# ADCs.net
KiCad netlist of a schematic drawn in Altium Designer
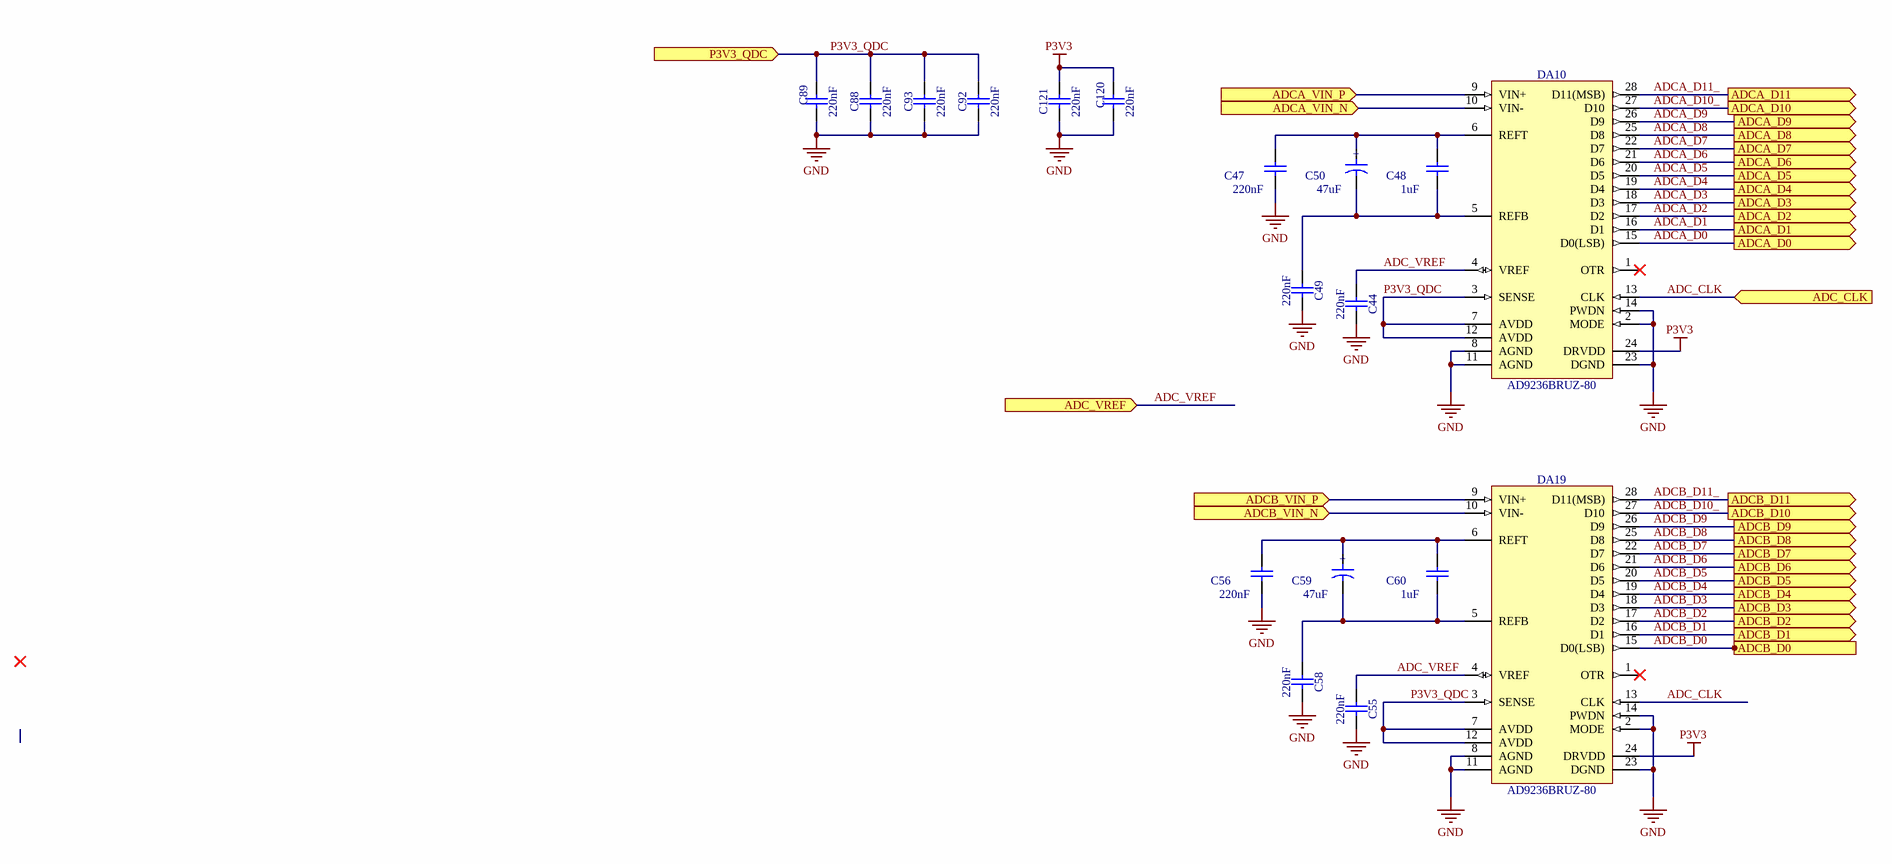
[diagram p0: ADCs.SchDoc]

(export (version "E")
  (design (tool "Eeschema 10.0.6"))
  (components
    (comp (ref "C44")
      (value "220nF")
      (footprint "CAPC2012X135N")
      (description "Non-polarised capacitor")
      (fields
        (field (name "PART NUMBER") "CC0805_220NF_50V_10%_X7R")
        (field (name "VOLTAGE") "50V")
        (field (name "AUTHOR") "CERN DEM JLC")
      )
      (libsource (lib "Capacitors") (part "Capacitor - non polarized"))
    )
    (comp (ref "C47")
      (value "220nF")
      (footprint "CAPC2012X135N")
      (description "Non-polarised capacitor")
      (fields
        (field (name "PART NUMBER") "CC0805_220NF_50V_10%_X7R")
        (field (name "VOLTAGE") "50V")
        (field (name "AUTHOR") "CERN DEM JLC")
      )
      (libsource (lib "Capacitors") (part "Capacitor - non polarized"))
    )
    (comp (ref "C48")
      (value "1uF")
      (footprint "CAPC2012X140N")
      (description "Non-polarised capacitor")
      (fields
        (field (name "PART NUMBER") "CC0805_1UF_25V_10%_X7R")
        (field (name "VOLTAGE") "25V")
        (field (name "AUTHOR") "CERN DEM JLC")
      )
      (libsource (lib "Capacitors") (part "Capacitor - non polarized"))
    )
    (comp (ref "C49")
      (value "220nF")
      (footprint "CAPC2012X135N")
      (description "Non-polarised capacitor")
      (fields
        (field (name "PART NUMBER") "CC0805_220NF_50V_10%_X7R")
        (field (name "VOLTAGE") "50V")
        (field (name "AUTHOR") "CERN DEM JLC")
      )
      (libsource (lib "Capacitors") (part "Capacitor - non polarized"))
    )
    (comp (ref "C50")
      (value "47uF")
      (footprint "CAPMP3528X120N")
      (description "Polarised capacitor")
      (fields
        (field (name "PART NUMBER") "CTE3528-12_47UF_10V_20%_PANASONIC_TPG")
        (field (name "VOLTAGE") "10V")
        (field (name "AUTHOR") "CERN DEM JLC")
      )
      (libsource (lib "Capacitors") (part "Capacitor - polarized"))
    )
    (comp (ref "C55")
      (value "220nF")
      (footprint "CAPC2012X135N")
      (description "Non-polarised capacitor")
      (fields
        (field (name "PART NUMBER") "CC0805_220NF_50V_10%_X7R")
        (field (name "VOLTAGE") "50V")
        (field (name "AUTHOR") "CERN DEM JLC")
      )
      (libsource (lib "Capacitors") (part "Capacitor - non polarized"))
    )
    (comp (ref "C56")
      (value "220nF")
      (footprint "CAPC2012X135N")
      (description "Non-polarised capacitor")
      (fields
        (field (name "PART NUMBER") "CC0805_220NF_50V_10%_X7R")
        (field (name "VOLTAGE") "50V")
        (field (name "AUTHOR") "CERN DEM JLC")
      )
      (libsource (lib "Capacitors") (part "Capacitor - non polarized"))
    )
    (comp (ref "C58")
      (value "220nF")
      (footprint "CAPC2012X135N")
      (description "Non-polarised capacitor")
      (fields
        (field (name "PART NUMBER") "CC0805_220NF_50V_10%_X7R")
        (field (name "VOLTAGE") "50V")
        (field (name "AUTHOR") "CERN DEM JLC")
      )
      (libsource (lib "Capacitors") (part "Capacitor - non polarized"))
    )
    (comp (ref "C59")
      (value "47uF")
      (footprint "CAPMP3528X120N")
      (description "Polarised capacitor")
      (fields
        (field (name "PART NUMBER") "CTE3528-12_47UF_10V_20%_PANASONIC_TPG")
        (field (name "VOLTAGE") "10V")
        (field (name "AUTHOR") "CERN DEM JLC")
      )
      (libsource (lib "Capacitors") (part "Capacitor - polarized"))
    )
    (comp (ref "C60")
      (value "1uF")
      (footprint "CAPC2012X140N")
      (description "Non-polarised capacitor")
      (fields
        (field (name "PART NUMBER") "CC0805_1UF_25V_10%_X7R")
        (field (name "VOLTAGE") "25V")
        (field (name "AUTHOR") "CERN DEM JLC")
      )
      (libsource (lib "Capacitors") (part "Capacitor - non polarized"))
    )
    (comp (ref "C88")
      (value "220nF")
      (footprint "CAPC2012X135N")
      (description "Non-polarised capacitor")
      (fields
        (field (name "PART NUMBER") "CC0805_220NF_50V_10%_X7R")
        (field (name "VOLTAGE") "50V")
        (field (name "AUTHOR") "CERN DEM JLC")
      )
      (libsource (lib "Capacitors") (part "Capacitor - non polarized"))
    )
    (comp (ref "C89")
      (value "220nF")
      (footprint "CAPC2012X135N")
      (description "Non-polarised capacitor")
      (fields
        (field (name "PART NUMBER") "CC0805_220NF_50V_10%_X7R")
        (field (name "VOLTAGE") "50V")
        (field (name "AUTHOR") "CERN DEM JLC")
      )
      (libsource (lib "Capacitors") (part "Capacitor - non polarized"))
    )
    (comp (ref "C92")
      (value "220nF")
      (footprint "CAPC2012X135N")
      (description "Non-polarised capacitor")
      (fields
        (field (name "PART NUMBER") "CC0805_220NF_50V_10%_X7R")
        (field (name "VOLTAGE") "50V")
        (field (name "AUTHOR") "CERN DEM JLC")
      )
      (libsource (lib "Capacitors") (part "Capacitor - non polarized"))
    )
    (comp (ref "C93")
      (value "220nF")
      (footprint "CAPC2012X135N")
      (description "Non-polarised capacitor")
      (fields
        (field (name "PART NUMBER") "CC0805_220NF_50V_10%_X7R")
        (field (name "VOLTAGE") "50V")
        (field (name "AUTHOR") "CERN DEM JLC")
      )
      (libsource (lib "Capacitors") (part "Capacitor - non polarized"))
    )
    (comp (ref "C120")
      (value "220nF")
      (footprint "CAPC2012X135N")
      (description "Non-polarised capacitor")
      (fields
        (field (name "PART NUMBER") "CC0805_220NF_50V_10%_X7R")
        (field (name "VOLTAGE") "50V")
        (field (name "AUTHOR") "CERN DEM JLC")
      )
      (libsource (lib "Capacitors") (part "Capacitor - non polarized"))
    )
    (comp (ref "C121")
      (value "220nF")
      (footprint "CAPC2012X135N")
      (description "Non-polarised capacitor")
      (fields
        (field (name "PART NUMBER") "CC0805_220NF_50V_10%_X7R")
        (field (name "VOLTAGE") "50V")
        (field (name "AUTHOR") "CERN DEM JLC")
      )
      (libsource (lib "Capacitors") (part "Capacitor - non polarized"))
    )
    (comp (ref "DA10")
      (value "AD9236BRUZ-80")
      (footprint "SOP65P640X120-28N")
      (description "12-Bit, 80 MSPS 3 V ADC")
      (fields
        (field (name "MANUFACTURER") "ANALOG DEVICES")
        (field (name "MANUFACTURER PART NUMBER") "AD9235BRUZ-40")
        (field (name "AUTHOR") "CERN DEM HF")
      )
      (libsource (lib "ICs And Semiconductors") (part "AD9236BRU"))
    )
    (comp (ref "DA19")
      (value "AD9236BRUZ-80")
      (footprint "SOP65P640X120-28N")
      (description "12-Bit, 80 MSPS 3 V ADC")
      (fields
        (field (name "MANUFACTURER") "ANALOG DEVICES")
        (field (name "MANUFACTURER PART NUMBER") "AD9235BRUZ-40")
        (field (name "AUTHOR") "CERN DEM HF")
      )
      (libsource (lib "ICs And Semiconductors") (part "AD9236BRU"))
    )
  )
  (nets
    (net (code "1") (name "/ADCA_D0") (class "Default")
      (node (ref "DA10") (pin "15") (pinfunction "D0(LSB)_15") (pintype "output"))
    )
    (net (code "2") (name "/ADCA_D1") (class "Default")
      (node (ref "DA10") (pin "16") (pinfunction "D1_16") (pintype "output"))
    )
    (net (code "3") (name "/ADCA_D2") (class "Default")
      (node (ref "DA10") (pin "17") (pinfunction "D2_17") (pintype "output"))
    )
    (net (code "4") (name "/ADCA_D3") (class "Default")
      (node (ref "DA10") (pin "18") (pinfunction "D3_18") (pintype "output"))
    )
    (net (code "5") (name "/ADCA_D4") (class "Default")
      (node (ref "DA10") (pin "19") (pinfunction "D4_19") (pintype "output"))
    )
    (net (code "6") (name "/ADCA_D5") (class "Default")
      (node (ref "DA10") (pin "20") (pinfunction "D5_20") (pintype "output"))
    )
    (net (code "7") (name "/ADCA_D6") (class "Default")
      (node (ref "DA10") (pin "21") (pinfunction "D6_21") (pintype "output"))
    )
    (net (code "8") (name "/ADCA_D7") (class "Default")
      (node (ref "DA10") (pin "22") (pinfunction "D7_22") (pintype "output"))
    )
    (net (code "9") (name "/ADCA_D8") (class "Default")
      (node (ref "DA10") (pin "25") (pinfunction "D8_25") (pintype "output"))
    )
    (net (code "10") (name "/ADCA_D9") (class "Default")
      (node (ref "DA10") (pin "26") (pinfunction "D9_26") (pintype "output"))
    )
    (net (code "11") (name "/ADCA_D10_") (class "Default")
      (node (ref "DA10") (pin "27") (pinfunction "D10_27") (pintype "output"))
    )
    (net (code "12") (name "/ADCA_D11_") (class "Default")
      (node (ref "DA10") (pin "28") (pinfunction "D11(MSB)_28") (pintype "output"))
    )
    (net (code "13") (name "/ADCA_VIN_N") (class "Default")
      (node (ref "DA10") (pin "10") (pinfunction "VIN-_10") (pintype "input"))
    )
    (net (code "14") (name "/ADCA_VIN_P") (class "Default")
      (node (ref "DA10") (pin "9") (pinfunction "VIN+_9") (pintype "input"))
    )
    (net (code "15") (name "/ADCB_D0") (class "Default")
      (node (ref "DA19") (pin "15") (pinfunction "D0(LSB)_15") (pintype "output"))
    )
    (net (code "16") (name "/ADCB_D1") (class "Default")
      (node (ref "DA19") (pin "16") (pinfunction "D1_16") (pintype "output"))
    )
    (net (code "17") (name "/ADCB_D2") (class "Default")
      (node (ref "DA19") (pin "17") (pinfunction "D2_17") (pintype "output"))
    )
    (net (code "18") (name "/ADCB_D3") (class "Default")
      (node (ref "DA19") (pin "18") (pinfunction "D3_18") (pintype "output"))
    )
    (net (code "19") (name "/ADCB_D4") (class "Default")
      (node (ref "DA19") (pin "19") (pinfunction "D4_19") (pintype "output"))
    )
    (net (code "20") (name "/ADCB_D5") (class "Default")
      (node (ref "DA19") (pin "20") (pinfunction "D5_20") (pintype "output"))
    )
    (net (code "21") (name "/ADCB_D6") (class "Default")
      (node (ref "DA19") (pin "21") (pinfunction "D6_21") (pintype "output"))
    )
    (net (code "22") (name "/ADCB_D7") (class "Default")
      (node (ref "DA19") (pin "22") (pinfunction "D7_22") (pintype "output"))
    )
    (net (code "23") (name "/ADCB_D8") (class "Default")
      (node (ref "DA19") (pin "25") (pinfunction "D8_25") (pintype "output"))
    )
    (net (code "24") (name "/ADCB_D9") (class "Default")
      (node (ref "DA19") (pin "26") (pinfunction "D9_26") (pintype "output"))
    )
    (net (code "25") (name "/ADCB_D10_") (class "Default")
      (node (ref "DA19") (pin "27") (pinfunction "D10_27") (pintype "output"))
    )
    (net (code "26") (name "/ADCB_D11_") (class "Default")
      (node (ref "DA19") (pin "28") (pinfunction "D11(MSB)_28") (pintype "output"))
    )
    (net (code "27") (name "/ADCB_VIN_N") (class "Default")
      (node (ref "DA19") (pin "10") (pinfunction "VIN-_10") (pintype "input"))
    )
    (net (code "28") (name "/ADCB_VIN_P") (class "Default")
      (node (ref "DA19") (pin "9") (pinfunction "VIN+_9") (pintype "input"))
    )
    (net (code "29") (name "/ADC_CLK") (class "Default")
      (node (ref "DA10") (pin "13") (pinfunction "CLK_13") (pintype "input"))
      (node (ref "DA19") (pin "13") (pinfunction "CLK_13") (pintype "input"))
    )
    (net (code "30") (name "/ADC_VREF") (class "Default")
      (node (ref "C44") (pin "2") (pinfunction "2_2") (pintype "passive"))
      (node (ref "C55") (pin "2") (pinfunction "2_2") (pintype "passive"))
      (node (ref "DA10") (pin "4") (pinfunction "VREF_4") (pintype "bidirectional"))
      (node (ref "DA19") (pin "4") (pinfunction "VREF_4") (pintype "bidirectional"))
    )
    (net (code "31") (name "/P3V3_QDC") (class "Default")
      (node (ref "C88") (pin "2") (pinfunction "2_2") (pintype "passive"))
      (node (ref "C89") (pin "2") (pinfunction "2_2") (pintype "passive"))
      (node (ref "C92") (pin "2") (pinfunction "2_2") (pintype "passive"))
      (node (ref "C93") (pin "2") (pinfunction "2_2") (pintype "passive"))
      (node (ref "DA10") (pin "12") (pinfunction "AVDD_12") (pintype "power_in"))
      (node (ref "DA10") (pin "3") (pinfunction "SENSE_3") (pintype "input"))
      (node (ref "DA10") (pin "7") (pinfunction "AVDD_7") (pintype "power_in"))
      (node (ref "DA19") (pin "12") (pinfunction "AVDD_12") (pintype "power_in"))
      (node (ref "DA19") (pin "3") (pinfunction "SENSE_3") (pintype "input"))
      (node (ref "DA19") (pin "7") (pinfunction "AVDD_7") (pintype "power_in"))
    )
    (net (code "32") (name "GND") (class "Default")
      (node (ref "C120") (pin "1") (pinfunction "1_1") (pintype "passive"))
      (node (ref "C121") (pin "1") (pinfunction "1_1") (pintype "passive"))
      (node (ref "C44") (pin "1") (pinfunction "1_1") (pintype "passive"))
      (node (ref "C47") (pin "1") (pinfunction "1_1") (pintype "passive"))
      (node (ref "C49") (pin "1") (pinfunction "1_1") (pintype "passive"))
      (node (ref "C55") (pin "1") (pinfunction "1_1") (pintype "passive"))
      (node (ref "C56") (pin "1") (pinfunction "1_1") (pintype "passive"))
      (node (ref "C58") (pin "1") (pinfunction "1_1") (pintype "passive"))
      (node (ref "C88") (pin "1") (pinfunction "1_1") (pintype "passive"))
      (node (ref "C89") (pin "1") (pinfunction "1_1") (pintype "passive"))
      (node (ref "C92") (pin "1") (pinfunction "1_1") (pintype "passive"))
      (node (ref "C93") (pin "1") (pinfunction "1_1") (pintype "passive"))
      (node (ref "DA10") (pin "11") (pinfunction "AGND_11") (pintype "power_in"))
      (node (ref "DA10") (pin "14") (pinfunction "PWDN_14") (pintype "input"))
      (node (ref "DA10") (pin "2") (pinfunction "MODE_2") (pintype "input"))
      (node (ref "DA10") (pin "23") (pinfunction "DGND_23") (pintype "power_in"))
      (node (ref "DA10") (pin "8") (pinfunction "AGND_8") (pintype "power_in"))
      (node (ref "DA19") (pin "11") (pinfunction "AGND_11") (pintype "power_in"))
      (node (ref "DA19") (pin "14") (pinfunction "PWDN_14") (pintype "input"))
      (node (ref "DA19") (pin "2") (pinfunction "MODE_2") (pintype "input"))
      (node (ref "DA19") (pin "23") (pinfunction "DGND_23") (pintype "power_in"))
      (node (ref "DA19") (pin "8") (pinfunction "AGND_8") (pintype "power_in"))
    )
    (net (code "33") (name "Net-(DA10-REFB)") (class "Default")
      (node (ref "C48") (pin "1") (pinfunction "1_1") (pintype "passive"))
      (node (ref "C49") (pin "2") (pinfunction "2_2") (pintype "passive"))
      (node (ref "C50") (pin "2") (pinfunction "2_2") (pintype "passive"))
      (node (ref "DA10") (pin "5") (pinfunction "REFB_5") (pintype "passive"))
    )
    (net (code "34") (name "Net-(DA10-REFT)") (class "Default")
      (node (ref "C47") (pin "2") (pinfunction "2_2") (pintype "passive"))
      (node (ref "C48") (pin "2") (pinfunction "2_2") (pintype "passive"))
      (node (ref "C50") (pin "1") (pinfunction "1_1") (pintype "passive"))
      (node (ref "DA10") (pin "6") (pinfunction "REFT_6") (pintype "passive"))
    )
    (net (code "35") (name "Net-(DA19-REFB)") (class "Default")
      (node (ref "C58") (pin "2") (pinfunction "2_2") (pintype "passive"))
      (node (ref "C59") (pin "2") (pinfunction "2_2") (pintype "passive"))
      (node (ref "C60") (pin "1") (pinfunction "1_1") (pintype "passive"))
      (node (ref "DA19") (pin "5") (pinfunction "REFB_5") (pintype "passive"))
    )
    (net (code "36") (name "Net-(DA19-REFT)") (class "Default")
      (node (ref "C56") (pin "2") (pinfunction "2_2") (pintype "passive"))
      (node (ref "C59") (pin "1") (pinfunction "1_1") (pintype "passive"))
      (node (ref "C60") (pin "2") (pinfunction "2_2") (pintype "passive"))
      (node (ref "DA19") (pin "6") (pinfunction "REFT_6") (pintype "passive"))
    )
    (net (code "37") (name "P3V3") (class "Default")
      (node (ref "C120") (pin "2") (pinfunction "2_2") (pintype "passive"))
      (node (ref "C121") (pin "2") (pinfunction "2_2") (pintype "passive"))
      (node (ref "DA10") (pin "24") (pinfunction "DRVDD_24") (pintype "power_in"))
      (node (ref "DA19") (pin "24") (pinfunction "DRVDD_24") (pintype "power_in"))
    )
    (net (code "38") (name "unconnected-(DA10-OTR-Pad1)") (class "Default")
      (node (ref "DA10") (pin "1") (pinfunction "OTR_1") (pintype "output+no_connect"))
    )
    (net (code "39") (name "unconnected-(DA19-OTR-Pad1)") (class "Default")
      (node (ref "DA19") (pin "1") (pinfunction "OTR_1") (pintype "output+no_connect"))
    )
  )
)
